# mux_gate.net
KiCad netlist of a schematic drawn in Altium Designer
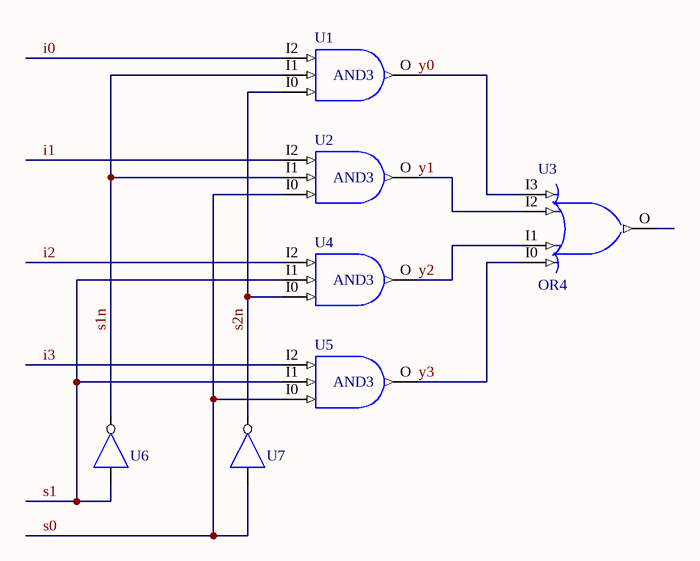
[diagram p0: mux_gate.SchDoc]

(export (version "E")
  (design (tool "Eeschema 10.0.6"))
  (components
    (comp (ref "U1")
      (value "AND3")
      (description "3-Input AND Gate")
      (fields (field (name "PUBLISHER") "Altium Limited"))
      (libsource (lib "CUPL PLD Programming") (part "AND3"))
    )
    (comp (ref "U2")
      (value "AND3")
      (description "3-Input AND Gate")
      (fields (field (name "PUBLISHER") "Altium Limited"))
      (libsource (lib "CUPL PLD Programming") (part "AND3"))
    )
    (comp (ref "U3")
      (value "OR4")
      (description "4-Input OR Gate")
      (fields (field (name "PUBLISHER") "Altium Limited"))
      (libsource (lib "CUPL PLD Programming") (part "OR4"))
    )
    (comp (ref "U4")
      (value "AND3")
      (description "3-Input AND Gate")
      (fields (field (name "PUBLISHER") "Altium Limited"))
      (libsource (lib "CUPL PLD Programming") (part "AND3"))
    )
    (comp (ref "U5")
      (value "AND3")
      (description "3-Input AND Gate")
      (fields (field (name "PUBLISHER") "Altium Limited"))
      (libsource (lib "CUPL PLD Programming") (part "AND3"))
    )
    (comp (ref "U6")
      (value "not")
      (description "1-bit General Purpose (Non-inverting) Buffer")
      (libsource (lib "BlockSchematics (DESKTOP-V82PM3U conflicted copy 2020-01-27 14 16 44)") (part "BUF"))
    )
    (comp (ref "U7")
      (value "not")
      (description "1-bit General Purpose (Non-inverting) Buffer")
      (libsource (lib "BlockSchematics (DESKTOP-V82PM3U conflicted copy 2020-01-27 14 16 44)") (part "BUF"))
    )
  )
  (nets
    (net (code "1") (name "/i0") (class "Default")
      (node (ref "U1") (pin "I2") (pinfunction "I2_I2") (pintype "input"))
    )
    (net (code "2") (name "/i1") (class "Default")
      (node (ref "U2") (pin "I2") (pinfunction "I2_I2") (pintype "input"))
    )
    (net (code "3") (name "/i2") (class "Default")
      (node (ref "U4") (pin "I2") (pinfunction "I2_I2") (pintype "input"))
    )
    (net (code "4") (name "/i3") (class "Default")
      (node (ref "U5") (pin "I2") (pinfunction "I2_I2") (pintype "input"))
    )
    (net (code "5") (name "/s0") (class "Default")
      (node (ref "U2") (pin "I0") (pinfunction "I0_I0") (pintype "input"))
      (node (ref "U5") (pin "I0") (pinfunction "I0_I0") (pintype "input"))
      (node (ref "U7") (pin "i") (pinfunction "i_i") (pintype "passive"))
    )
    (net (code "6") (name "/s1") (class "Default")
      (node (ref "U4") (pin "I1") (pinfunction "I1_I1") (pintype "input"))
      (node (ref "U5") (pin "I1") (pinfunction "I1_I1") (pintype "input"))
      (node (ref "U6") (pin "i") (pinfunction "i_i") (pintype "passive"))
    )
    (net (code "7") (name "/s1n") (class "Default")
      (node (ref "U1") (pin "I1") (pinfunction "I1_I1") (pintype "input"))
      (node (ref "U2") (pin "I1") (pinfunction "I1_I1") (pintype "input"))
      (node (ref "U6") (pin "o") (pinfunction "o_o") (pintype "passive"))
    )
    (net (code "8") (name "/s2n") (class "Default")
      (node (ref "U1") (pin "I0") (pinfunction "I0_I0") (pintype "input"))
      (node (ref "U4") (pin "I0") (pinfunction "I0_I0") (pintype "input"))
      (node (ref "U7") (pin "o") (pinfunction "o_o") (pintype "passive"))
    )
    (net (code "9") (name "/y0") (class "Default")
      (node (ref "U1") (pin "O") (pinfunction "O_O") (pintype "output"))
      (node (ref "U3") (pin "I3") (pinfunction "I3_I3") (pintype "input"))
    )
    (net (code "10") (name "/y1") (class "Default")
      (node (ref "U2") (pin "O") (pinfunction "O_O") (pintype "output"))
      (node (ref "U3") (pin "I2") (pinfunction "I2_I2") (pintype "input"))
    )
    (net (code "11") (name "/y2") (class "Default")
      (node (ref "U3") (pin "I1") (pinfunction "I1_I1") (pintype "input"))
      (node (ref "U4") (pin "O") (pinfunction "O_O") (pintype "output"))
    )
    (net (code "12") (name "/y3") (class "Default")
      (node (ref "U3") (pin "I0") (pinfunction "I0_I0") (pintype "input"))
      (node (ref "U5") (pin "O") (pinfunction "O_O") (pintype "output"))
    )
    (net (code "13") (name "unconnected-(U3-PadO)") (class "Default")
      (node (ref "U3") (pin "O") (pinfunction "O_O") (pintype "output"))
    )
  )
)
